# I2c_Digipot.net
KiCad netlist of a schematic drawn in EAGLE
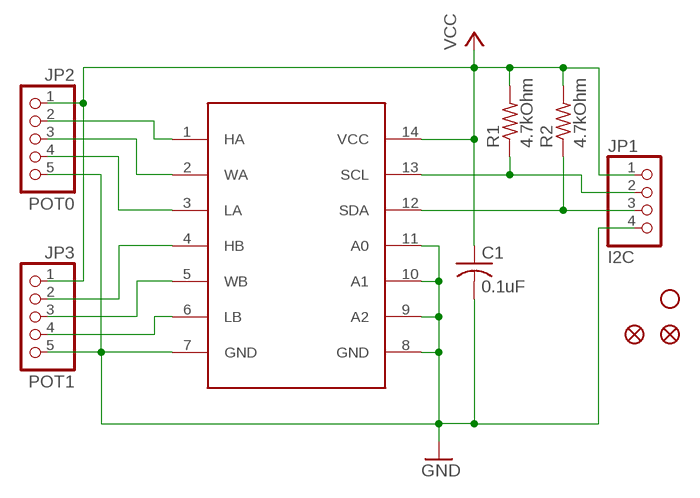
[diagram p0: schematic, sheet 1]

(export (version "E")
  (design (tool "Eeschema 10.0.6"))
  (components
    (comp (ref "C1")
      (value "0.1uF")
      (footprint "eagle-import:C1206")
      (libsource (lib "eagle-import") (part "C-USC1206"))
    )
    (comp (ref "JP1")
      (value "I2C")
      (footprint "eagle-import:1X04")
      (libsource (lib "eagle-import") (part "PINHD-1X4"))
    )
    (comp (ref "JP2")
      (value "POT0")
      (footprint "eagle-import:1X05")
      (libsource (lib "eagle-import") (part "PINHD-1X5"))
    )
    (comp (ref "JP3")
      (value "POT1")
      (footprint "eagle-import:1X05")
      (libsource (lib "eagle-import") (part "PINHD-1X5"))
    )
    (comp (ref "JP5")
      (value "STAND-OFF")
      (footprint "eagle-import:STAND-OFF")
      (libsource (lib "eagle-import") (part "STAND-OFF"))
    )
    (comp (ref "JP6")
      (value "FIDUCIAL1X2")
      (footprint "eagle-import:FIDUCIAL-1X2")
      (libsource (lib "eagle-import") (part "FIDUCIAL1X2"))
    )
    (comp (ref "JP7")
      (value "FIDUCIAL1X2")
      (footprint "eagle-import:FIDUCIAL-1X2")
      (libsource (lib "eagle-import") (part "FIDUCIAL1X2"))
    )
    (comp (ref "R1")
      (value "4.7kOhm")
      (footprint "eagle-import:R1206")
      (libsource (lib "eagle-import") (part "R-US_R1206"))
    )
    (comp (ref "R2")
      (value "4.7kOhm")
      (footprint "eagle-import:R1206")
      (libsource (lib "eagle-import") (part "R-US_R1206"))
    )
    (comp (ref "U1")
      (value "MAX5387")
      (footprint "eagle-import:TSSOP14")
      (libsource (lib "eagle-import") (part "MAX5387"))
    )
  )
  (nets
    (net (code "1") (name "GND") (class "Default")
      (node (ref "C1") (pin "2") (pinfunction "2_2") (pintype "passive"))
      (node (ref "JP1") (pin "4") (pinfunction "4_4") (pintype "passive"))
      (node (ref "JP2") (pin "5") (pinfunction "5_5") (pintype "passive"))
      (node (ref "JP3") (pin "5") (pinfunction "5_5") (pintype "passive"))
      (node (ref "U1") (pin "10") (pinfunction "A1_10") (pintype "input"))
      (node (ref "U1") (pin "11") (pinfunction "A0_11") (pintype "input"))
      (node (ref "U1") (pin "7") (pinfunction "GND_7") (pintype "power_in"))
      (node (ref "U1") (pin "8") (pinfunction "GND_8") (pintype "power_in"))
      (node (ref "U1") (pin "9") (pinfunction "A2_9") (pintype "input"))
    )
    (net (code "2") (name "Net-(U1-HA)") (class "Default")
      (node (ref "JP2") (pin "2") (pinfunction "2_2") (pintype "passive"))
      (node (ref "U1") (pin "1") (pinfunction "HA_1") (pintype "passive"))
    )
    (net (code "3") (name "Net-(U1-HB)") (class "Default")
      (node (ref "JP3") (pin "2") (pinfunction "2_2") (pintype "passive"))
      (node (ref "U1") (pin "4") (pinfunction "HB_4") (pintype "passive"))
    )
    (net (code "4") (name "Net-(U1-LA)") (class "Default")
      (node (ref "JP2") (pin "4") (pinfunction "4_4") (pintype "passive"))
      (node (ref "U1") (pin "3") (pinfunction "LA_3") (pintype "passive"))
    )
    (net (code "5") (name "Net-(U1-LB)") (class "Default")
      (node (ref "JP3") (pin "4") (pinfunction "4_4") (pintype "passive"))
      (node (ref "U1") (pin "6") (pinfunction "LB_6") (pintype "passive"))
    )
    (net (code "6") (name "Net-(U1-SCL)") (class "Default")
      (node (ref "JP1") (pin "2") (pinfunction "2_2") (pintype "passive"))
      (node (ref "R1") (pin "1") (pinfunction "1_1") (pintype "passive"))
      (node (ref "U1") (pin "13") (pinfunction "SCL_13") (pintype "input"))
    )
    (net (code "7") (name "Net-(U1-SDA)") (class "Default")
      (node (ref "JP1") (pin "3") (pinfunction "3_3") (pintype "passive"))
      (node (ref "R2") (pin "1") (pinfunction "1_1") (pintype "passive"))
      (node (ref "U1") (pin "12") (pinfunction "SDA_12") (pintype "bidirectional"))
    )
    (net (code "8") (name "Net-(U1-WA)") (class "Default")
      (node (ref "JP2") (pin "3") (pinfunction "3_3") (pintype "passive"))
      (node (ref "U1") (pin "2") (pinfunction "WA_2") (pintype "passive"))
    )
    (net (code "9") (name "Net-(U1-WB)") (class "Default")
      (node (ref "JP3") (pin "3") (pinfunction "3_3") (pintype "passive"))
      (node (ref "U1") (pin "5") (pinfunction "WB_5") (pintype "passive"))
    )
    (net (code "10") (name "VCC") (class "Default")
      (node (ref "C1") (pin "1") (pinfunction "1_1") (pintype "passive"))
      (node (ref "JP1") (pin "1") (pinfunction "1_1") (pintype "passive"))
      (node (ref "JP2") (pin "1") (pinfunction "1_1") (pintype "passive"))
      (node (ref "JP3") (pin "1") (pinfunction "1_1") (pintype "passive"))
      (node (ref "R1") (pin "2") (pinfunction "2_2") (pintype "passive"))
      (node (ref "R2") (pin "2") (pinfunction "2_2") (pintype "passive"))
      (node (ref "U1") (pin "14") (pinfunction "VCC_14") (pintype "power_in"))
    )
  )
)
